# diode_rectifier.net
KiCad netlist of a schematic drawn in EAGLE
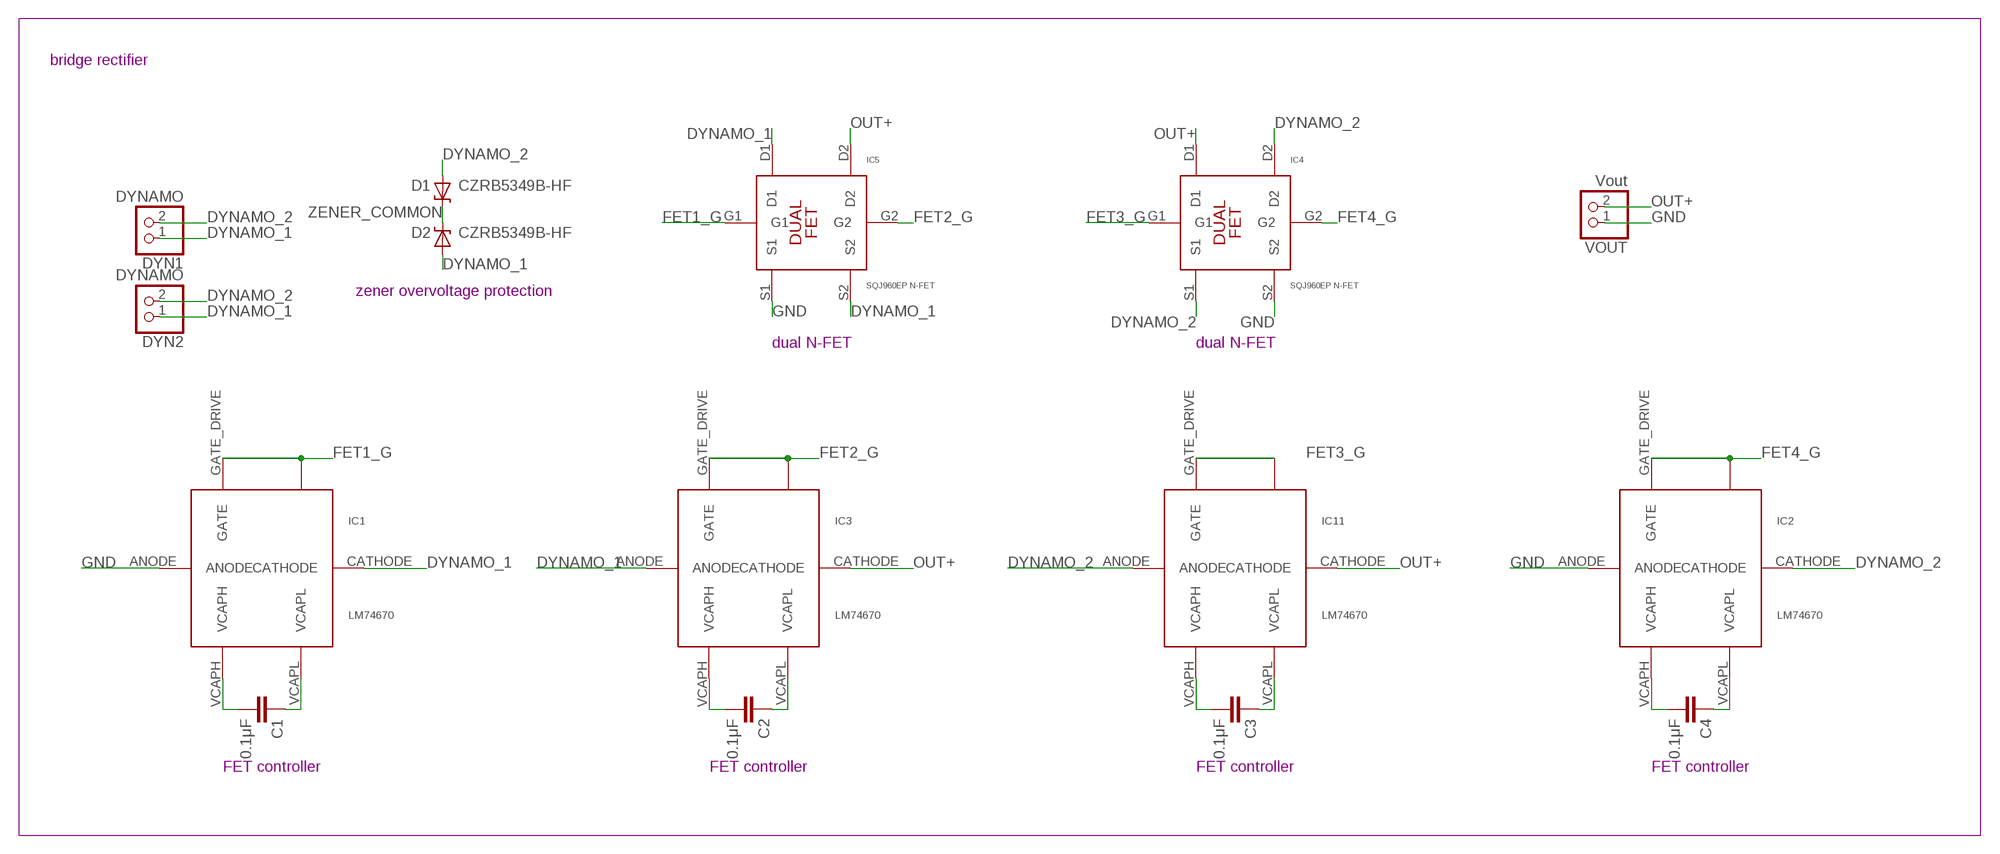
[diagram p0: schematic, sheet 1]

(export (version "E")
  (design (tool "Eeschema 10.0.6"))
  (components
    (comp (ref "C1")
      (value "0.1μF")
      (footprint "eagle-import:C0805")
      (libsource (lib "eagle-import") (part "C-EUC0805"))
    )
    (comp (ref "C2")
      (value "0.1μF")
      (footprint "eagle-import:C0805")
      (libsource (lib "eagle-import") (part "C-EUC0805"))
    )
    (comp (ref "C3")
      (value "0.1μF")
      (footprint "eagle-import:C0805")
      (libsource (lib "eagle-import") (part "C-EUC0805"))
    )
    (comp (ref "C4")
      (value "0.1μF")
      (footprint "eagle-import:C0805")
      (libsource (lib "eagle-import") (part "C-EUC0805"))
    )
    (comp (ref "D1")
      (value "CZRB5349B-HF")
      (footprint "eagle-import:DO-214")
      (libsource (lib "eagle-import") (part "ZENER"))
    )
    (comp (ref "D2")
      (value "CZRB5349B-HF")
      (footprint "eagle-import:DO-214")
      (libsource (lib "eagle-import") (part "ZENER"))
    )
    (comp (ref "DYN1")
      (value "DYNAMO")
      (footprint "eagle-import:1X02")
      (libsource (lib "eagle-import") (part "PINHD-1X2"))
    )
    (comp (ref "DYN2")
      (value "DYNAMO")
      (footprint "eagle-import:1X02")
      (libsource (lib "eagle-import") (part "PINHD-1X2"))
    )
    (comp (ref "IC1")
      (value "LM74670")
      (footprint "eagle-import:VSSOP-8")
      (libsource (lib "eagle-import") (part "LM74670"))
    )
    (comp (ref "IC2")
      (value "LM74670")
      (footprint "eagle-import:VSSOP-8")
      (libsource (lib "eagle-import") (part "LM74670"))
    )
    (comp (ref "IC3")
      (value "LM74670")
      (footprint "eagle-import:VSSOP-8")
      (libsource (lib "eagle-import") (part "LM74670"))
    )
    (comp (ref "IC4")
      (value "SQJ960EP N-FET")
      (footprint "eagle-import:SO-8L")
      (libsource (lib "eagle-import") (part "SQJ96XEP"))
    )
    (comp (ref "IC5")
      (value "SQJ960EP N-FET")
      (footprint "eagle-import:SO-8L")
      (libsource (lib "eagle-import") (part "SQJ96XEP"))
    )
    (comp (ref "IC11")
      (value "LM74670")
      (footprint "eagle-import:VSSOP-8")
      (libsource (lib "eagle-import") (part "LM74670"))
    )
    (comp (ref "VOUT")
      (value "Vout")
      (footprint "eagle-import:1X02")
      (libsource (lib "eagle-import") (part "PINHD-1X2"))
    )
  )
  (nets
    (net (code "1") (name "/DYNAMO_1") (class "Default")
      (node (ref "D2") (pin "AN") (pinfunction "AN_AN") (pintype "passive"))
      (node (ref "DYN1") (pin "1") (pinfunction "1_1") (pintype "passive"))
      (node (ref "DYN2") (pin "1") (pinfunction "1_1") (pintype "passive"))
      (node (ref "IC1") (pin "CATHODE") (pinfunction "CATHODE_CATHODE") (pintype "bidirectional"))
      (node (ref "IC3") (pin "ANODE") (pinfunction "ANODE_ANODE") (pintype "bidirectional"))
      (node (ref "IC5") (pin "D1") (pinfunction "D1_D1") (pintype "bidirectional"))
      (node (ref "IC5") (pin "S2") (pinfunction "S2_S2") (pintype "bidirectional"))
    )
    (net (code "2") (name "/DYNAMO_2") (class "Default")
      (node (ref "D1") (pin "AN") (pinfunction "AN_AN") (pintype "passive"))
      (node (ref "DYN1") (pin "2") (pinfunction "2_2") (pintype "passive"))
      (node (ref "DYN2") (pin "2") (pinfunction "2_2") (pintype "passive"))
      (node (ref "IC11") (pin "ANODE") (pinfunction "ANODE_ANODE") (pintype "bidirectional"))
      (node (ref "IC2") (pin "CATHODE") (pinfunction "CATHODE_CATHODE") (pintype "bidirectional"))
      (node (ref "IC4") (pin "D2") (pinfunction "D2_D2") (pintype "bidirectional"))
      (node (ref "IC4") (pin "S1") (pinfunction "S1_S1") (pintype "bidirectional"))
    )
    (net (code "3") (name "/FET1_G") (class "Default")
      (node (ref "IC1") (pin "GATE_DRIVE") (pinfunction "GATE_GATE_DRIVE") (pintype "bidirectional"))
      (node (ref "IC1") (pin "GATE_PULLD") (pinfunction "GATE_PULLD_GATE_PULLD") (pintype "bidirectional"))
      (node (ref "IC5") (pin "G1") (pinfunction "G1_G1") (pintype "bidirectional"))
    )
    (net (code "4") (name "/FET2_G") (class "Default")
      (node (ref "IC3") (pin "GATE_DRIVE") (pinfunction "GATE_GATE_DRIVE") (pintype "bidirectional"))
      (node (ref "IC3") (pin "GATE_PULLD") (pinfunction "GATE_PULLD_GATE_PULLD") (pintype "bidirectional"))
      (node (ref "IC5") (pin "G2") (pinfunction "G2_G2") (pintype "bidirectional"))
    )
    (net (code "5") (name "/FET3_G") (class "Default")
      (node (ref "IC11") (pin "GATE_DRIVE") (pinfunction "GATE_GATE_DRIVE") (pintype "bidirectional"))
      (node (ref "IC11") (pin "GATE_PULLD") (pinfunction "GATE_PULLD_GATE_PULLD") (pintype "bidirectional"))
      (node (ref "IC4") (pin "G1") (pinfunction "G1_G1") (pintype "bidirectional"))
    )
    (net (code "6") (name "/FET4_G") (class "Default")
      (node (ref "IC2") (pin "GATE_DRIVE") (pinfunction "GATE_GATE_DRIVE") (pintype "bidirectional"))
      (node (ref "IC2") (pin "GATE_PULLD") (pinfunction "GATE_PULLD_GATE_PULLD") (pintype "bidirectional"))
      (node (ref "IC4") (pin "G2") (pinfunction "G2_G2") (pintype "bidirectional"))
    )
    (net (code "7") (name "/GND") (class "Default")
      (node (ref "IC1") (pin "ANODE") (pinfunction "ANODE_ANODE") (pintype "bidirectional"))
      (node (ref "IC2") (pin "ANODE") (pinfunction "ANODE_ANODE") (pintype "bidirectional"))
      (node (ref "IC4") (pin "S2") (pinfunction "S2_S2") (pintype "bidirectional"))
      (node (ref "IC5") (pin "S1") (pinfunction "S1_S1") (pintype "bidirectional"))
      (node (ref "VOUT") (pin "1") (pinfunction "1_1") (pintype "passive"))
    )
    (net (code "8") (name "/OUT+") (class "Default")
      (node (ref "IC11") (pin "CATHODE") (pinfunction "CATHODE_CATHODE") (pintype "bidirectional"))
      (node (ref "IC3") (pin "CATHODE") (pinfunction "CATHODE_CATHODE") (pintype "bidirectional"))
      (node (ref "IC4") (pin "D1") (pinfunction "D1_D1") (pintype "bidirectional"))
      (node (ref "IC5") (pin "D2") (pinfunction "D2_D2") (pintype "bidirectional"))
      (node (ref "VOUT") (pin "2") (pinfunction "2_2") (pintype "passive"))
    )
    (net (code "9") (name "/ZENER_COMMON") (class "Default")
      (node (ref "D1") (pin "CAT") (pinfunction "CAT_CAT") (pintype "passive"))
      (node (ref "D2") (pin "CAT") (pinfunction "CAT_CAT") (pintype "passive"))
    )
    (net (code "10") (name "Net-(C1-Pad1)") (class "Default")
      (node (ref "C1") (pin "1") (pinfunction "1_1") (pintype "passive"))
      (node (ref "IC1") (pin "VCAPL") (pinfunction "VCAPL_VCAPL") (pintype "bidirectional"))
    )
    (net (code "11") (name "Net-(C1-Pad2)") (class "Default")
      (node (ref "C1") (pin "2") (pinfunction "2_2") (pintype "passive"))
      (node (ref "IC1") (pin "VCAPH") (pinfunction "VCAPH_VCAPH") (pintype "bidirectional"))
    )
    (net (code "12") (name "Net-(C2-Pad1)") (class "Default")
      (node (ref "C2") (pin "1") (pinfunction "1_1") (pintype "passive"))
      (node (ref "IC3") (pin "VCAPL") (pinfunction "VCAPL_VCAPL") (pintype "bidirectional"))
    )
    (net (code "13") (name "Net-(C2-Pad2)") (class "Default")
      (node (ref "C2") (pin "2") (pinfunction "2_2") (pintype "passive"))
      (node (ref "IC3") (pin "VCAPH") (pinfunction "VCAPH_VCAPH") (pintype "bidirectional"))
    )
    (net (code "14") (name "Net-(C3-Pad1)") (class "Default")
      (node (ref "C3") (pin "1") (pinfunction "1_1") (pintype "passive"))
      (node (ref "IC11") (pin "VCAPL") (pinfunction "VCAPL_VCAPL") (pintype "bidirectional"))
    )
    (net (code "15") (name "Net-(C3-Pad2)") (class "Default")
      (node (ref "C3") (pin "2") (pinfunction "2_2") (pintype "passive"))
      (node (ref "IC11") (pin "VCAPH") (pinfunction "VCAPH_VCAPH") (pintype "bidirectional"))
    )
    (net (code "16") (name "Net-(C4-Pad1)") (class "Default")
      (node (ref "C4") (pin "1") (pinfunction "1_1") (pintype "passive"))
      (node (ref "IC2") (pin "VCAPL") (pinfunction "VCAPL_VCAPL") (pintype "bidirectional"))
    )
    (net (code "17") (name "Net-(C4-Pad2)") (class "Default")
      (node (ref "C4") (pin "2") (pinfunction "2_2") (pintype "passive"))
      (node (ref "IC2") (pin "VCAPH") (pinfunction "VCAPH_VCAPH") (pintype "bidirectional"))
    )
  )
)
